# brain1_v11.net
KiCad netlist of a schematic drawn in EAGLE
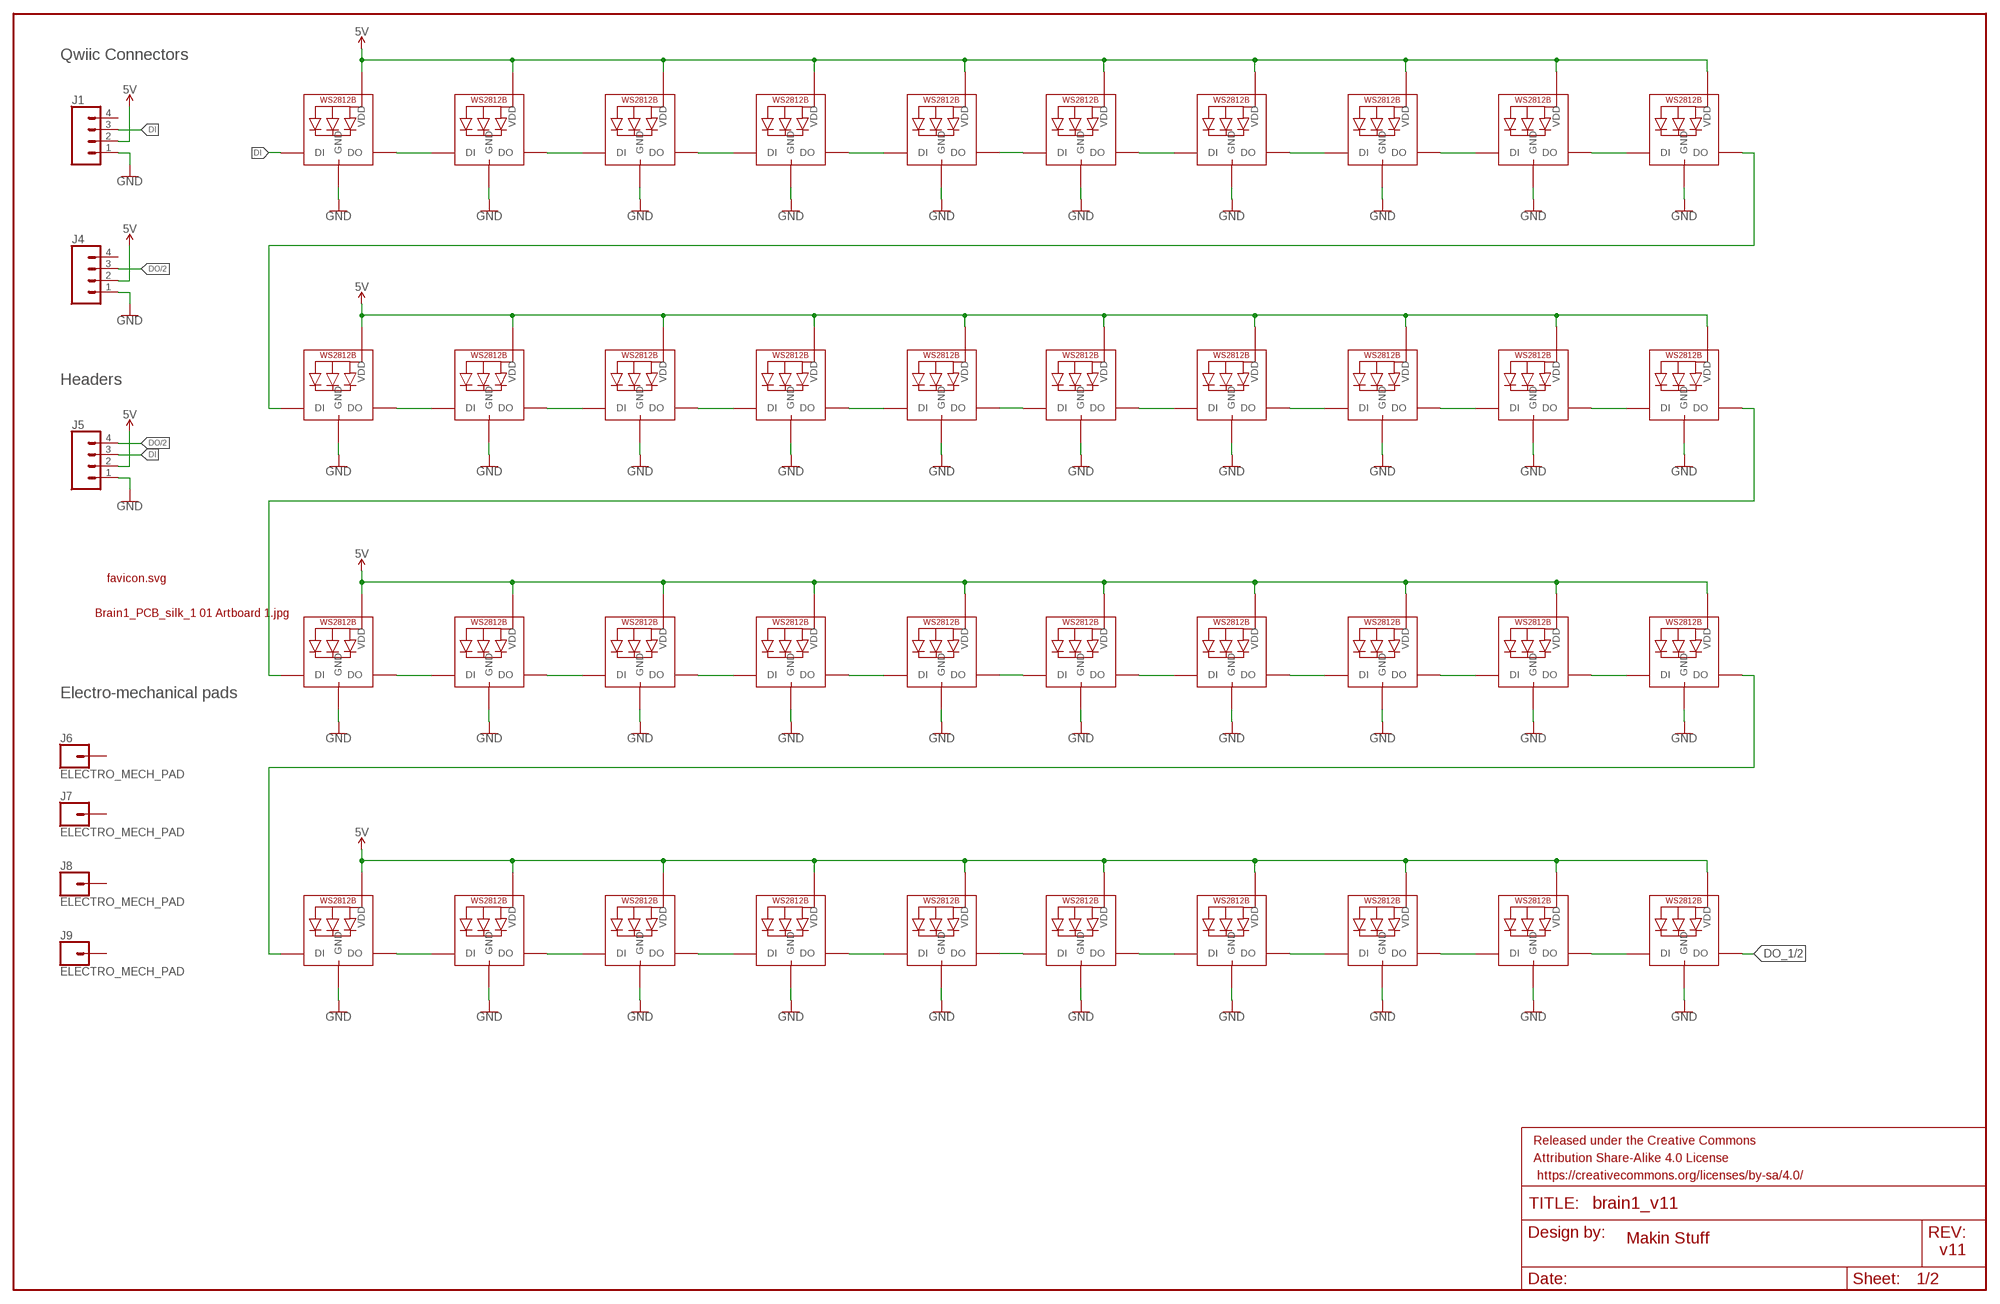
[diagram p0: schematic, sheet 1]
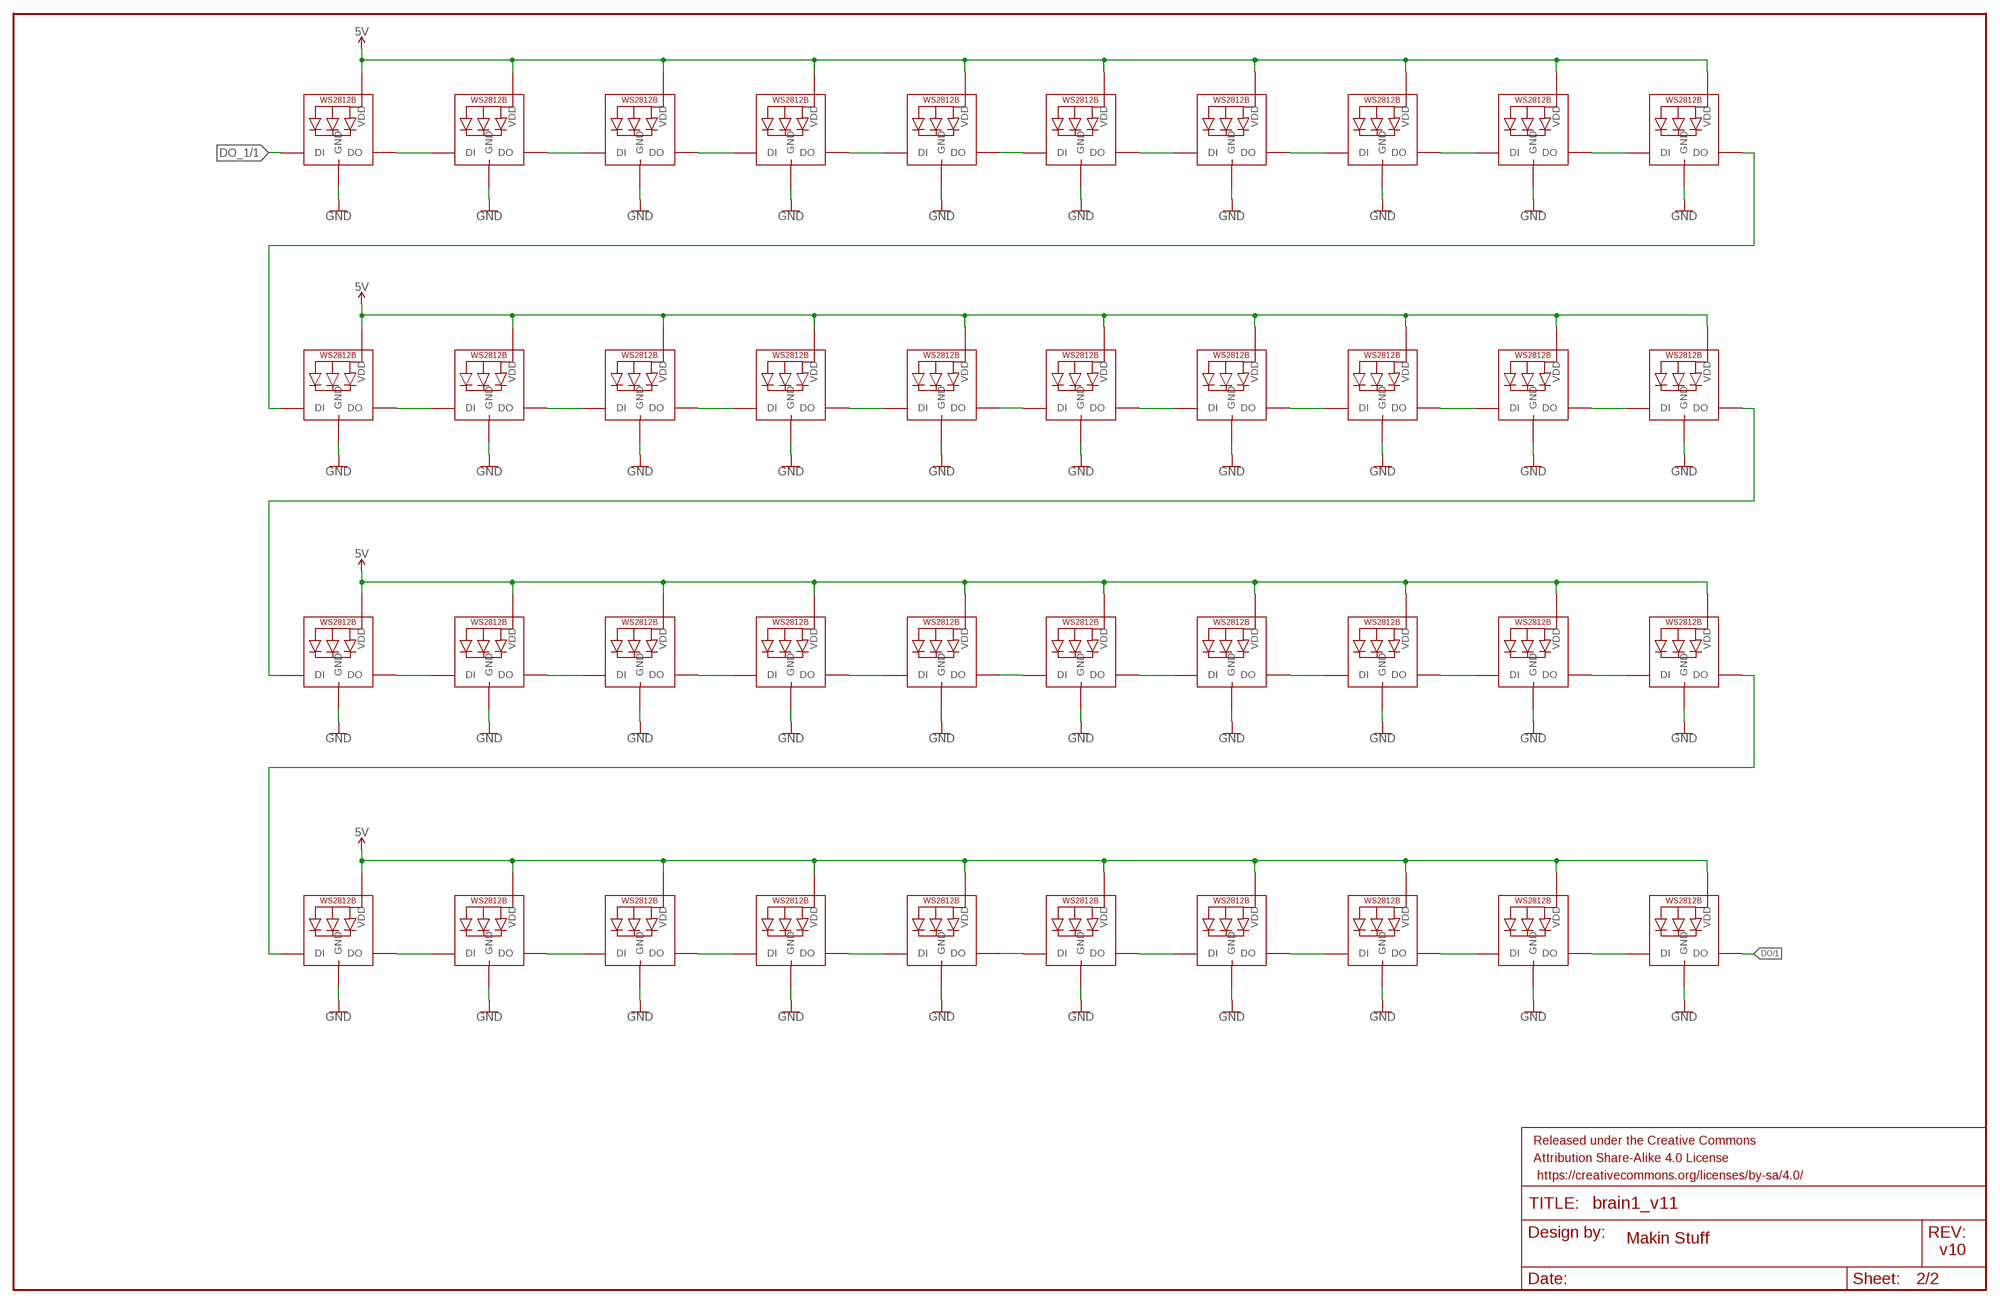
[diagram p1: schematic, sheet 2]

(export (version "E")
  (design (tool "Eeschema 10.0.6"))
  (components
    (comp (ref "FRAME1")
      (value "FRAME-LEDGER")
      (footprint "eagle-import:CREATIVE_COMMONS")
      (libsource (lib "eagle-import") (part "FRAME-LEDGER"))
    )
    (comp (ref "FRAME3")
      (value "FRAME-LEDGER")
      (footprint "eagle-import:CREATIVE_COMMONS")
      (libsource (lib "eagle-import") (part "FRAME-LEDGER"))
    )
    (comp (ref "LED41")
      (value "3.5X3.5_RGB_LED3.5X3.5")
      (footprint "eagle-import:3.5X3.5_RGB_LED")
      (libsource (lib "eagle-import") (part "3.5X3.5_RGB_LED3.5X3.5"))
    )
    (comp (ref "LED42")
      (value "3.5X3.5_RGB_LED3.5X3.5")
      (footprint "eagle-import:3.5X3.5_RGB_LED")
      (libsource (lib "eagle-import") (part "3.5X3.5_RGB_LED3.5X3.5"))
    )
    (comp (ref "LED43")
      (value "3.5X3.5_RGB_LED3.5X3.5")
      (footprint "eagle-import:3.5X3.5_RGB_LED")
      (libsource (lib "eagle-import") (part "3.5X3.5_RGB_LED3.5X3.5"))
    )
    (comp (ref "LED44")
      (value "3.5X3.5_RGB_LED3.5X3.5")
      (footprint "eagle-import:3.5X3.5_RGB_LED")
      (libsource (lib "eagle-import") (part "3.5X3.5_RGB_LED3.5X3.5"))
    )
    (comp (ref "LED45")
      (value "3.5X3.5_RGB_LED3.5X3.5")
      (footprint "eagle-import:3.5X3.5_RGB_LED")
      (libsource (lib "eagle-import") (part "3.5X3.5_RGB_LED3.5X3.5"))
    )
    (comp (ref "LED46")
      (value "3.5X3.5_RGB_LED3.5X3.5")
      (footprint "eagle-import:3.5X3.5_RGB_LED")
      (libsource (lib "eagle-import") (part "3.5X3.5_RGB_LED3.5X3.5"))
    )
    (comp (ref "LED47")
      (value "3.5X3.5_RGB_LED3.5X3.5")
      (footprint "eagle-import:3.5X3.5_RGB_LED")
      (libsource (lib "eagle-import") (part "3.5X3.5_RGB_LED3.5X3.5"))
    )
    (comp (ref "LED48")
      (value "3.5X3.5_RGB_LED3.5X3.5")
      (footprint "eagle-import:3.5X3.5_RGB_LED")
      (libsource (lib "eagle-import") (part "3.5X3.5_RGB_LED3.5X3.5"))
    )
    (comp (ref "LED49")
      (value "3.5X3.5_RGB_LED3.5X3.5")
      (footprint "eagle-import:3.5X3.5_RGB_LED")
      (libsource (lib "eagle-import") (part "3.5X3.5_RGB_LED3.5X3.5"))
    )
    (comp (ref "LED50")
      (value "3.5X3.5_RGB_LED3.5X3.5")
      (footprint "eagle-import:3.5X3.5_RGB_LED")
      (libsource (lib "eagle-import") (part "3.5X3.5_RGB_LED3.5X3.5"))
    )
    (comp (ref "LED51")
      (value "3.5X3.5_RGB_LED3.5X3.5")
      (footprint "eagle-import:3.5X3.5_RGB_LED")
      (libsource (lib "eagle-import") (part "3.5X3.5_RGB_LED3.5X3.5"))
    )
    (comp (ref "LED52")
      (value "3.5X3.5_RGB_LED3.5X3.5")
      (footprint "eagle-import:3.5X3.5_RGB_LED")
      (libsource (lib "eagle-import") (part "3.5X3.5_RGB_LED3.5X3.5"))
    )
    (comp (ref "LED53")
      (value "3.5X3.5_RGB_LED3.5X3.5")
      (footprint "eagle-import:3.5X3.5_RGB_LED")
      (libsource (lib "eagle-import") (part "3.5X3.5_RGB_LED3.5X3.5"))
    )
    (comp (ref "LED54")
      (value "3.5X3.5_RGB_LED3.5X3.5")
      (footprint "eagle-import:3.5X3.5_RGB_LED")
      (libsource (lib "eagle-import") (part "3.5X3.5_RGB_LED3.5X3.5"))
    )
    (comp (ref "LED55")
      (value "3.5X3.5_RGB_LED3.5X3.5")
      (footprint "eagle-import:3.5X3.5_RGB_LED")
      (libsource (lib "eagle-import") (part "3.5X3.5_RGB_LED3.5X3.5"))
    )
    (comp (ref "LED56")
      (value "3.5X3.5_RGB_LED3.5X3.5")
      (footprint "eagle-import:3.5X3.5_RGB_LED")
      (libsource (lib "eagle-import") (part "3.5X3.5_RGB_LED3.5X3.5"))
    )
    (comp (ref "LED57")
      (value "3.5X3.5_RGB_LED3.5X3.5")
      (footprint "eagle-import:3.5X3.5_RGB_LED")
      (libsource (lib "eagle-import") (part "3.5X3.5_RGB_LED3.5X3.5"))
    )
    (comp (ref "LED58")
      (value "3.5X3.5_RGB_LED3.5X3.5")
      (footprint "eagle-import:3.5X3.5_RGB_LED")
      (libsource (lib "eagle-import") (part "3.5X3.5_RGB_LED3.5X3.5"))
    )
    (comp (ref "LED59")
      (value "3.5X3.5_RGB_LED3.5X3.5")
      (footprint "eagle-import:3.5X3.5_RGB_LED")
      (libsource (lib "eagle-import") (part "3.5X3.5_RGB_LED3.5X3.5"))
    )
    (comp (ref "LED60")
      (value "3.5X3.5_RGB_LED3.5X3.5")
      (footprint "eagle-import:3.5X3.5_RGB_LED")
      (libsource (lib "eagle-import") (part "3.5X3.5_RGB_LED3.5X3.5"))
    )
    (comp (ref "LED61")
      (value "3.5X3.5_RGB_LED3.5X3.5")
      (footprint "eagle-import:3.5X3.5_RGB_LED")
      (libsource (lib "eagle-import") (part "3.5X3.5_RGB_LED3.5X3.5"))
    )
    (comp (ref "LED62")
      (value "3.5X3.5_RGB_LED3.5X3.5")
      (footprint "eagle-import:3.5X3.5_RGB_LED")
      (libsource (lib "eagle-import") (part "3.5X3.5_RGB_LED3.5X3.5"))
    )
    (comp (ref "LED63")
      (value "3.5X3.5_RGB_LED3.5X3.5")
      (footprint "eagle-import:3.5X3.5_RGB_LED")
      (libsource (lib "eagle-import") (part "3.5X3.5_RGB_LED3.5X3.5"))
    )
    (comp (ref "LED64")
      (value "3.5X3.5_RGB_LED3.5X3.5")
      (footprint "eagle-import:3.5X3.5_RGB_LED")
      (libsource (lib "eagle-import") (part "3.5X3.5_RGB_LED3.5X3.5"))
    )
    (comp (ref "LED65")
      (value "3.5X3.5_RGB_LED3.5X3.5")
      (footprint "eagle-import:3.5X3.5_RGB_LED")
      (libsource (lib "eagle-import") (part "3.5X3.5_RGB_LED3.5X3.5"))
    )
    (comp (ref "LED66")
      (value "3.5X3.5_RGB_LED3.5X3.5")
      (footprint "eagle-import:3.5X3.5_RGB_LED")
      (libsource (lib "eagle-import") (part "3.5X3.5_RGB_LED3.5X3.5"))
    )
    (comp (ref "LED67")
      (value "3.5X3.5_RGB_LED3.5X3.5")
      (footprint "eagle-import:3.5X3.5_RGB_LED")
      (libsource (lib "eagle-import") (part "3.5X3.5_RGB_LED3.5X3.5"))
    )
    (comp (ref "LED68")
      (value "3.5X3.5_RGB_LED3.5X3.5")
      (footprint "eagle-import:3.5X3.5_RGB_LED")
      (libsource (lib "eagle-import") (part "3.5X3.5_RGB_LED3.5X3.5"))
    )
    (comp (ref "LED69")
      (value "3.5X3.5_RGB_LED3.5X3.5")
      (footprint "eagle-import:3.5X3.5_RGB_LED")
      (libsource (lib "eagle-import") (part "3.5X3.5_RGB_LED3.5X3.5"))
    )
    (comp (ref "LED70")
      (value "3.5X3.5_RGB_LED3.5X3.5")
      (footprint "eagle-import:3.5X3.5_RGB_LED")
      (libsource (lib "eagle-import") (part "3.5X3.5_RGB_LED3.5X3.5"))
    )
    (comp (ref "LED71")
      (value "3.5X3.5_RGB_LED3.5X3.5")
      (footprint "eagle-import:3.5X3.5_RGB_LED")
      (libsource (lib "eagle-import") (part "3.5X3.5_RGB_LED3.5X3.5"))
    )
    (comp (ref "LED72")
      (value "3.5X3.5_RGB_LED3.5X3.5")
      (footprint "eagle-import:3.5X3.5_RGB_LED")
      (libsource (lib "eagle-import") (part "3.5X3.5_RGB_LED3.5X3.5"))
    )
    (comp (ref "LED73")
      (value "3.5X3.5_RGB_LED3.5X3.5")
      (footprint "eagle-import:3.5X3.5_RGB_LED")
      (libsource (lib "eagle-import") (part "3.5X3.5_RGB_LED3.5X3.5"))
    )
    (comp (ref "LED74")
      (value "3.5X3.5_RGB_LED3.5X3.5")
      (footprint "eagle-import:3.5X3.5_RGB_LED")
      (libsource (lib "eagle-import") (part "3.5X3.5_RGB_LED3.5X3.5"))
    )
    (comp (ref "LED75")
      (value "3.5X3.5_RGB_LED3.5X3.5")
      (footprint "eagle-import:3.5X3.5_RGB_LED")
      (libsource (lib "eagle-import") (part "3.5X3.5_RGB_LED3.5X3.5"))
    )
    (comp (ref "LED76")
      (value "3.5X3.5_RGB_LED3.5X3.5")
      (footprint "eagle-import:3.5X3.5_RGB_LED")
      (libsource (lib "eagle-import") (part "3.5X3.5_RGB_LED3.5X3.5"))
    )
    (comp (ref "LED77")
      (value "3.5X3.5_RGB_LED3.5X3.5")
      (footprint "eagle-import:3.5X3.5_RGB_LED")
      (libsource (lib "eagle-import") (part "3.5X3.5_RGB_LED3.5X3.5"))
    )
    (comp (ref "LED78")
      (value "3.5X3.5_RGB_LED3.5X3.5")
      (footprint "eagle-import:3.5X3.5_RGB_LED")
      (libsource (lib "eagle-import") (part "3.5X3.5_RGB_LED3.5X3.5"))
    )
    (comp (ref "LED79")
      (value "3.5X3.5_RGB_LED3.5X3.5")
      (footprint "eagle-import:3.5X3.5_RGB_LED")
      (libsource (lib "eagle-import") (part "3.5X3.5_RGB_LED3.5X3.5"))
    )
    (comp (ref "LED80")
      (value "3.5X3.5_RGB_LED3.5X3.5")
      (footprint "eagle-import:3.5X3.5_RGB_LED")
      (libsource (lib "eagle-import") (part "3.5X3.5_RGB_LED3.5X3.5"))
    )
    (comp (ref "FRAME2")
      (value "FRAME-LEDGER")
      (footprint "eagle-import:CREATIVE_COMMONS")
      (libsource (lib "eagle-import") (part "FRAME-LEDGER"))
    )
    (comp (ref "J1")
      (value "CONN_04SMD3")
      (footprint "eagle-import:JST04_1MM_RA")
      (libsource (lib "eagle-import") (part "CONN_04SMD3"))
    )
    (comp (ref "J4")
      (value "CONN_04SMD3")
      (footprint "eagle-import:JST04_1MM_RA")
      (libsource (lib "eagle-import") (part "CONN_04SMD3"))
    )
    (comp (ref "J5")
      (value "CONN_041X04_NO_SILK_NO_POP")
      (footprint "eagle-import:1X04_NO_SILK")
      (libsource (lib "eagle-import") (part "CONN_041X04_NO_SILK_NO_POP"))
    )
    (comp (ref "J6")
      (value "ELECTRO_MECH_PAD")
      (footprint "eagle-import:5X3_SOLDER_PAD")
      (libsource (lib "eagle-import") (part "ELECTRO_MECH_PAD"))
    )
    (comp (ref "J7")
      (value "ELECTRO_MECH_PAD")
      (footprint "eagle-import:5X3_SOLDER_PAD")
      (libsource (lib "eagle-import") (part "ELECTRO_MECH_PAD"))
    )
    (comp (ref "J8")
      (value "ELECTRO_MECH_PAD")
      (footprint "eagle-import:5X3_SOLDER_PAD")
      (libsource (lib "eagle-import") (part "ELECTRO_MECH_PAD"))
    )
    (comp (ref "J9")
      (value "ELECTRO_MECH_PAD")
      (footprint "eagle-import:5X3_SOLDER_PAD")
      (libsource (lib "eagle-import") (part "ELECTRO_MECH_PAD"))
    )
    (comp (ref "LED1")
      (value "3.5X3.5_RGB_LED3.5X3.5")
      (footprint "eagle-import:3.5X3.5_RGB_LED")
      (libsource (lib "eagle-import") (part "3.5X3.5_RGB_LED3.5X3.5"))
    )
    (comp (ref "LED2")
      (value "3.5X3.5_RGB_LED3.5X3.5")
      (footprint "eagle-import:3.5X3.5_RGB_LED")
      (libsource (lib "eagle-import") (part "3.5X3.5_RGB_LED3.5X3.5"))
    )
    (comp (ref "LED3")
      (value "3.5X3.5_RGB_LED3.5X3.5")
      (footprint "eagle-import:3.5X3.5_RGB_LED")
      (libsource (lib "eagle-import") (part "3.5X3.5_RGB_LED3.5X3.5"))
    )
    (comp (ref "LED4")
      (value "3.5X3.5_RGB_LED3.5X3.5")
      (footprint "eagle-import:3.5X3.5_RGB_LED")
      (libsource (lib "eagle-import") (part "3.5X3.5_RGB_LED3.5X3.5"))
    )
    (comp (ref "LED5")
      (value "3.5X3.5_RGB_LED3.5X3.5")
      (footprint "eagle-import:3.5X3.5_RGB_LED")
      (libsource (lib "eagle-import") (part "3.5X3.5_RGB_LED3.5X3.5"))
    )
    (comp (ref "LED6")
      (value "3.5X3.5_RGB_LED3.5X3.5")
      (footprint "eagle-import:3.5X3.5_RGB_LED")
      (libsource (lib "eagle-import") (part "3.5X3.5_RGB_LED3.5X3.5"))
    )
    (comp (ref "LED7")
      (value "3.5X3.5_RGB_LED3.5X3.5")
      (footprint "eagle-import:3.5X3.5_RGB_LED")
      (libsource (lib "eagle-import") (part "3.5X3.5_RGB_LED3.5X3.5"))
    )
    (comp (ref "LED8")
      (value "3.5X3.5_RGB_LED3.5X3.5")
      (footprint "eagle-import:3.5X3.5_RGB_LED")
      (libsource (lib "eagle-import") (part "3.5X3.5_RGB_LED3.5X3.5"))
    )
    (comp (ref "LED9")
      (value "3.5X3.5_RGB_LED3.5X3.5")
      (footprint "eagle-import:3.5X3.5_RGB_LED")
      (libsource (lib "eagle-import") (part "3.5X3.5_RGB_LED3.5X3.5"))
    )
    (comp (ref "LED10")
      (value "3.5X3.5_RGB_LED3.5X3.5")
      (footprint "eagle-import:3.5X3.5_RGB_LED")
      (libsource (lib "eagle-import") (part "3.5X3.5_RGB_LED3.5X3.5"))
    )
    (comp (ref "LED11")
      (value "3.5X3.5_RGB_LED3.5X3.5")
      (footprint "eagle-import:3.5X3.5_RGB_LED")
      (libsource (lib "eagle-import") (part "3.5X3.5_RGB_LED3.5X3.5"))
    )
    (comp (ref "LED12")
      (value "3.5X3.5_RGB_LED3.5X3.5")
      (footprint "eagle-import:3.5X3.5_RGB_LED")
      (libsource (lib "eagle-import") (part "3.5X3.5_RGB_LED3.5X3.5"))
    )
    (comp (ref "LED13")
      (value "3.5X3.5_RGB_LED3.5X3.5")
      (footprint "eagle-import:3.5X3.5_RGB_LED")
      (libsource (lib "eagle-import") (part "3.5X3.5_RGB_LED3.5X3.5"))
    )
    (comp (ref "LED14")
      (value "3.5X3.5_RGB_LED3.5X3.5")
      (footprint "eagle-import:3.5X3.5_RGB_LED")
      (libsource (lib "eagle-import") (part "3.5X3.5_RGB_LED3.5X3.5"))
    )
    (comp (ref "LED15")
      (value "3.5X3.5_RGB_LED3.5X3.5")
      (footprint "eagle-import:3.5X3.5_RGB_LED")
      (libsource (lib "eagle-import") (part "3.5X3.5_RGB_LED3.5X3.5"))
    )
    (comp (ref "LED16")
      (value "3.5X3.5_RGB_LED3.5X3.5")
      (footprint "eagle-import:3.5X3.5_RGB_LED")
      (libsource (lib "eagle-import") (part "3.5X3.5_RGB_LED3.5X3.5"))
    )
    (comp (ref "LED17")
      (value "3.5X3.5_RGB_LED3.5X3.5")
      (footprint "eagle-import:3.5X3.5_RGB_LED")
      (libsource (lib "eagle-import") (part "3.5X3.5_RGB_LED3.5X3.5"))
    )
    (comp (ref "LED18")
      (value "3.5X3.5_RGB_LED3.5X3.5")
      (footprint "eagle-import:3.5X3.5_RGB_LED")
      (libsource (lib "eagle-import") (part "3.5X3.5_RGB_LED3.5X3.5"))
    )
    (comp (ref "LED19")
      (value "3.5X3.5_RGB_LED3.5X3.5")
      (footprint "eagle-import:3.5X3.5_RGB_LED")
      (libsource (lib "eagle-import") (part "3.5X3.5_RGB_LED3.5X3.5"))
    )
    (comp (ref "LED20")
      (value "3.5X3.5_RGB_LED3.5X3.5")
      (footprint "eagle-import:3.5X3.5_RGB_LED")
      (libsource (lib "eagle-import") (part "3.5X3.5_RGB_LED3.5X3.5"))
    )
    (comp (ref "LED21")
      (value "3.5X3.5_RGB_LED3.5X3.5")
      (footprint "eagle-import:3.5X3.5_RGB_LED")
      (libsource (lib "eagle-import") (part "3.5X3.5_RGB_LED3.5X3.5"))
    )
    (comp (ref "LED22")
      (value "3.5X3.5_RGB_LED3.5X3.5")
      (footprint "eagle-import:3.5X3.5_RGB_LED")
      (libsource (lib "eagle-import") (part "3.5X3.5_RGB_LED3.5X3.5"))
    )
    (comp (ref "LED23")
      (value "3.5X3.5_RGB_LED3.5X3.5")
      (footprint "eagle-import:3.5X3.5_RGB_LED")
      (libsource (lib "eagle-import") (part "3.5X3.5_RGB_LED3.5X3.5"))
    )
    (comp (ref "LED24")
      (value "3.5X3.5_RGB_LED3.5X3.5")
      (footprint "eagle-import:3.5X3.5_RGB_LED")
      (libsource (lib "eagle-import") (part "3.5X3.5_RGB_LED3.5X3.5"))
    )
    (comp (ref "LED25")
      (value "3.5X3.5_RGB_LED3.5X3.5")
      (footprint "eagle-import:3.5X3.5_RGB_LED")
      (libsource (lib "eagle-import") (part "3.5X3.5_RGB_LED3.5X3.5"))
    )
    (comp (ref "LED26")
      (value "3.5X3.5_RGB_LED3.5X3.5")
      (footprint "eagle-import:3.5X3.5_RGB_LED")
      (libsource (lib "eagle-import") (part "3.5X3.5_RGB_LED3.5X3.5"))
    )
    (comp (ref "LED27")
      (value "3.5X3.5_RGB_LED3.5X3.5")
      (footprint "eagle-import:3.5X3.5_RGB_LED")
      (libsource (lib "eagle-import") (part "3.5X3.5_RGB_LED3.5X3.5"))
    )
    (comp (ref "LED28")
      (value "3.5X3.5_RGB_LED3.5X3.5")
      (footprint "eagle-import:3.5X3.5_RGB_LED")
      (libsource (lib "eagle-import") (part "3.5X3.5_RGB_LED3.5X3.5"))
    )
    (comp (ref "LED29")
      (value "3.5X3.5_RGB_LED3.5X3.5")
      (footprint "eagle-import:3.5X3.5_RGB_LED")
      (libsource (lib "eagle-import") (part "3.5X3.5_RGB_LED3.5X3.5"))
    )
    (comp (ref "LED30")
      (value "3.5X3.5_RGB_LED3.5X3.5")
      (footprint "eagle-import:3.5X3.5_RGB_LED")
      (libsource (lib "eagle-import") (part "3.5X3.5_RGB_LED3.5X3.5"))
    )
    (comp (ref "LED31")
      (value "3.5X3.5_RGB_LED3.5X3.5")
      (footprint "eagle-import:3.5X3.5_RGB_LED")
      (libsource (lib "eagle-import") (part "3.5X3.5_RGB_LED3.5X3.5"))
    )
    (comp (ref "LED32")
      (value "3.5X3.5_RGB_LED3.5X3.5")
      (footprint "eagle-import:3.5X3.5_RGB_LED")
      (libsource (lib "eagle-import") (part "3.5X3.5_RGB_LED3.5X3.5"))
    )
    (comp (ref "LED33")
      (value "3.5X3.5_RGB_LED3.5X3.5")
      (footprint "eagle-import:3.5X3.5_RGB_LED")
      (libsource (lib "eagle-import") (part "3.5X3.5_RGB_LED3.5X3.5"))
    )
    (comp (ref "LED34")
      (value "3.5X3.5_RGB_LED3.5X3.5")
      (footprint "eagle-import:3.5X3.5_RGB_LED")
      (libsource (lib "eagle-import") (part "3.5X3.5_RGB_LED3.5X3.5"))
    )
    (comp (ref "LED35")
      (value "3.5X3.5_RGB_LED3.5X3.5")
      (footprint "eagle-import:3.5X3.5_RGB_LED")
      (libsource (lib "eagle-import") (part "3.5X3.5_RGB_LED3.5X3.5"))
    )
    (comp (ref "LED36")
      (value "3.5X3.5_RGB_LED3.5X3.5")
      (footprint "eagle-import:3.5X3.5_RGB_LED")
      (libsource (lib "eagle-import") (part "3.5X3.5_RGB_LED3.5X3.5"))
    )
    (comp (ref "LED37")
      (value "3.5X3.5_RGB_LED3.5X3.5")
      (footprint "eagle-import:3.5X3.5_RGB_LED")
      (libsource (lib "eagle-import") (part "3.5X3.5_RGB_LED3.5X3.5"))
    )
    (comp (ref "LED38")
      (value "3.5X3.5_RGB_LED3.5X3.5")
      (footprint "eagle-import:3.5X3.5_RGB_LED")
      (libsource (lib "eagle-import") (part "3.5X3.5_RGB_LED3.5X3.5"))
    )
    (comp (ref "LED39")
      (value "3.5X3.5_RGB_LED3.5X3.5")
      (footprint "eagle-import:3.5X3.5_RGB_LED")
      (libsource (lib "eagle-import") (part "3.5X3.5_RGB_LED3.5X3.5"))
    )
    (comp (ref "LED40")
      (value "3.5X3.5_RGB_LED3.5X3.5")
      (footprint "eagle-import:3.5X3.5_RGB_LED")
      (libsource (lib "eagle-import") (part "3.5X3.5_RGB_LED3.5X3.5"))
    )
    (comp (ref "U$1")
      (value "FAVICON#SVG")
      (footprint "eagle-import:FAVICON#SVG")
      (libsource (lib "eagle-import") (part "FAVICON#SVG"))
    )
    (comp (ref "U$2")
      (value "BRAIN1_PCB_SILK_1_01_ARTBOARD_1#JPG")
      (footprint "eagle-import:BRAIN1_PCB_SILK_1_01_ARTBOARD_1#JPG")
      (libsource (lib "eagle-import") (part "BRAIN1_PCB_SILK_1_01_ARTBOARD_1#JPG"))
    )
  )
  (nets
    (net (code "1") (name "5V") (class "Default")
      (node (ref "J1") (pin "2") (pinfunction "2_2") (pintype "passive"))
      (node (ref "J4") (pin "2") (pinfunction "2_2") (pintype "passive"))
      (node (ref "J5") (pin "2") (pinfunction "2_2") (pintype "passive"))
      (node (ref "LED1") (pin "4") (pinfunction "VDD_4") (pintype "power_in"))
      (node (ref "LED10") (pin "4") (pinfunction "VDD_4") (pintype "power_in"))
      (node (ref "LED11") (pin "4") (pinfunction "VDD_4") (pintype "power_in"))
      (node (ref "LED12") (pin "4") (pinfunction "VDD_4") (pintype "power_in"))
      (node (ref "LED13") (pin "4") (pinfunction "VDD_4") (pintype "power_in"))
      (node (ref "LED14") (pin "4") (pinfunction "VDD_4") (pintype "power_in"))
      (node (ref "LED15") (pin "4") (pinfunction "VDD_4") (pintype "power_in"))
      (node (ref "LED16") (pin "4") (pinfunction "VDD_4") (pintype "power_in"))
      (node (ref "LED17") (pin "4") (pinfunction "VDD_4") (pintype "power_in"))
      (node (ref "LED18") (pin "4") (pinfunction "VDD_4") (pintype "power_in"))
      (node (ref "LED19") (pin "4") (pinfunction "VDD_4") (pintype "power_in"))
      (node (ref "LED2") (pin "4") (pinfunction "VDD_4") (pintype "power_in"))
      (node (ref "LED20") (pin "4") (pinfunction "VDD_4") (pintype "power_in"))
      (node (ref "LED21") (pin "4") (pinfunction "VDD_4") (pintype "power_in"))
      (node (ref "LED22") (pin "4") (pinfunction "VDD_4") (pintype "power_in"))
      (node (ref "LED23") (pin "4") (pinfunction "VDD_4") (pintype "power_in"))
      (node (ref "LED24") (pin "4") (pinfunction "VDD_4") (pintype "power_in"))
      (node (ref "LED25") (pin "4") (pinfunction "VDD_4") (pintype "power_in"))
      (node (ref "LED26") (pin "4") (pinfunction "VDD_4") (pintype "power_in"))
      (node (ref "LED27") (pin "4") (pinfunction "VDD_4") (pintype "power_in"))
      (node (ref "LED28") (pin "4") (pinfunction "VDD_4") (pintype "power_in"))
      (node (ref "LED29") (pin "4") (pinfunction "VDD_4") (pintype "power_in"))
      (node (ref "LED3") (pin "4") (pinfunction "VDD_4") (pintype "power_in"))
      (node (ref "LED30") (pin "4") (pinfunction "VDD_4") (pintype "power_in"))
      (node (ref "LED31") (pin "4") (pinfunction "VDD_4") (pintype "power_in"))
      (node (ref "LED32") (pin "4") (pinfunction "VDD_4") (pintype "power_in"))
      (node (ref "LED33") (pin "4") (pinfunction "VDD_4") (pintype "power_in"))
      (node (ref "LED34") (pin "4") (pinfunction "VDD_4") (pintype "power_in"))
      (node (ref "LED35") (pin "4") (pinfunction "VDD_4") (pintype "power_in"))
      (node (ref "LED36") (pin "4") (pinfunction "VDD_4") (pintype "power_in"))
      (node (ref "LED37") (pin "4") (pinfunction "VDD_4") (pintype "power_in"))
      (node (ref "LED38") (pin "4") (pinfunction "VDD_4") (pintype "power_in"))
      (node (ref "LED39") (pin "4") (pinfunction "VDD_4") (pintype "power_in"))
      (node (ref "LED4") (pin "4") (pinfunction "VDD_4") (pintype "power_in"))
      (node (ref "LED40") (pin "4") (pinfunction "VDD_4") (pintype "power_in"))
      (node (ref "LED41") (pin "4") (pinfunction "VDD_4") (pintype "power_in"))
      (node (ref "LED42") (pin "4") (pinfunction "VDD_4") (pintype "power_in"))
      (node (ref "LED43") (pin "4") (pinfunction "VDD_4") (pintype "power_in"))
      (node (ref "LED44") (pin "4") (pinfunction "VDD_4") (pintype "power_in"))
      (node (ref "LED45") (pin "4") (pinfunction "VDD_4") (pintype "power_in"))
      (node (ref "LED46") (pin "4") (pinfunction "VDD_4") (pintype "power_in"))
      (node (ref "LED47") (pin "4") (pinfunction "VDD_4") (pintype "power_in"))
      (node (ref "LED48") (pin "4") (pinfunction "VDD_4") (pintype "power_in"))
      (node (ref "LED49") (pin "4") (pinfunction "VDD_4") (pintype "power_in"))
      (node (ref "LED5") (pin "4") (pinfunction "VDD_4") (pintype "power_in"))
      (node (ref "LED50") (pin "4") (pinfunction "VDD_4") (pintype "power_in"))
      (node (ref "LED51") (pin "4") (pinfunction "VDD_4") (pintype "power_in"))
      (node (ref "LED52") (pin "4") (pinfunction "VDD_4") (pintype "power_in"))
      (node (ref "LED53") (pin "4") (pinfunction "VDD_4") (pintype "power_in"))
      (node (ref "LED54") (pin "4") (pinfunction "VDD_4") (pintype "power_in"))
      (node (ref "LED55") (pin "4") (pinfunction "VDD_4") (pintype "power_in"))
      (node (ref "LED56") (pin "4") (pinfunction "VDD_4") (pintype "power_in"))
      (node (ref "LED57") (pin "4") (pinfunction "VDD_4") (pintype "power_in"))
      (node (ref "LED58") (pin "4") (pinfunction "VDD_4") (pintype "power_in"))
      (node (ref "LED59") (pin "4") (pinfunction "VDD_4") (pintype "power_in"))
      (node (ref "LED6") (pin "4") (pinfunction "VDD_4") (pintype "power_in"))
      (node (ref "LED60") (pin "4") (pinfunction "VDD_4") (pintype "power_in"))
      (node (ref "LED61") (pin "4") (pinfunction "VDD_4") (pintype "power_in"))
      (node (ref "LED62") (pin "4") (pinfunction "VDD_4") (pintype "power_in"))
      (node (ref "LED63") (pin "4") (pinfunction "VDD_4") (pintype "power_in"))
      (node (ref "LED64") (pin "4") (pinfunction "VDD_4") (pintype "power_in"))
      (node (ref "LED65") (pin "4") (pinfunction "VDD_4") (pintype "power_in"))
      (node (ref "LED66") (pin "4") (pinfunction "VDD_4") (pintype "power_in"))
      (node (ref "LED67") (pin "4") (pinfunction "VDD_4") (pintype "power_in"))
      (node (ref "LED68") (pin "4") (pinfunction "VDD_4") (pintype "power_in"))
      (node (ref "LED69") (pin "4") (pinfunction "VDD_4") (pintype "power_in"))
      (node (ref "LED7") (pin "4") (pinfunction "VDD_4") (pintype "power_in"))
      (node (ref "LED70") (pin "4") (pinfunction "VDD_4") (pintype "power_in"))
      (node (ref "LED71") (pin "4") (pinfunction "VDD_4") (pintype "power_in"))
      (node (ref "LED72") (pin "4") (pinfunction "VDD_4") (pintype "power_in"))
      (node (ref "LED73") (pin "4") (pinfunction "VDD_4") (pintype "power_in"))
      (node (ref "LED74") (pin "4") (pinfunction "VDD_4") (pintype "power_in"))
      (node (ref "LED75") (pin "4") (pinfunction "VDD_4") (pintype "power_in"))
      (node (ref "LED76") (pin "4") (pinfunction "VDD_4") (pintype "power_in"))
      (node (ref "LED77") (pin "4") (pinfunction "VDD_4") (pintype "power_in"))
      (node (ref "LED78") (pin "4") (pinfunction "VDD_4") (pintype "power_in"))
      (node (ref "LED79") (pin "4") (pinfunction "VDD_4") (pintype "power_in"))
      (node (ref "LED8") (pin "4") (pinfunction "VDD_4") (pintype "power_in"))
      (node (ref "LED80") (pin "4") (pinfunction "VDD_4") (pintype "power_in"))
      (node (ref "LED9") (pin "4") (pinfunction "VDD_4") (pintype "power_in"))
    )
    (net (code "2") (name "DI") (class "Default")
      (node (ref "J1") (pin "3") (pinfunction "3_3") (pintype "passive"))
      (node (ref "J5") (pin "3") (pinfunction "3_3") (pintype "passive"))
      (node (ref "LED1") (pin "3") (pinfunction "DI_3") (pintype "input"))
    )
    (net (code "3") (name "DO") (class "Default")
      (node (ref "J4") (pin "3") (pinfunction "3_3") (pintype "passive"))
      (node (ref "J5") (pin "4") (pinfunction "4_4") (pintype "passive"))
      (node (ref "LED80") (pin "1") (pinfunction "DO_1") (pintype "output"))
    )
    (net (code "4") (name "DO_1") (class "Default")
      (node (ref "LED40") (pin "1") (pinfunction "DO_1") (pintype "output"))
      (node (ref "LED41") (pin "3") (pinfunction "DI_3") (pintype "input"))
    )
    (net (code "5") (name "GND") (class "Default")
      (node (ref "J1") (pin "1") (pinfunction "1_1") (pintype "passive"))
      (node (ref "J4") (pin "1") (pinfunction "1_1") (pintype "passive"))
      (node (ref "J5") (pin "1") (pinfunction "1_1") (pintype "passive"))
      (node (ref "LED1") (pin "2") (pinfunction "GND_2") (pintype "power_in"))
      (node (ref "LED10") (pin "2") (pinfunction "GND_2") (pintype "power_in"))
      (node (ref "LED11") (pin "2") (pinfunction "GND_2") (pintype "power_in"))
      (node (ref "LED12") (pin "2") (pinfunction "GND_2") (pintype "power_in"))
      (node (ref "LED13") (pin "2") (pinfunction "GND_2") (pintype "power_in"))
      (node (ref "LED14") (pin "2") (pinfunction "GND_2") (pintype "power_in"))
      (node (ref "LED15") (pin "2") (pinfunction "GND_2") (pintype "power_in"))
      (node (ref "LED16") (pin "2") (pinfunction "GND_2") (pintype "power_in"))
      (node (ref "LED17") (pin "2") (pinfunction "GND_2") (pintype "power_in"))
      (node (ref "LED18") (pin "2") (pinfunction "GND_2") (pintype "power_in"))
      (node (ref "LED19") (pin "2") (pinfunction "GND_2") (pintype "power_in"))
      (node (ref "LED2") (pin "2") (pinfunction "GND_2") (pintype "power_in"))
      (node (ref "LED20") (pin "2") (pinfunction "GND_2") (pintype "power_in"))
      (node (ref "LED21") (pin "2") (pinfunction "GND_2") (pintype "power_in"))
      (node (ref "LED22") (pin "2") (pinfunction "GND_2") (pintype "power_in"))
      (node (ref "LED23") (pin "2") (pinfunction "GND_2") (pintype "power_in"))
      (node (ref "LED24") (pin "2") (pinfunction "GND_2") (pintype "power_in"))
      (node (ref "LED25") (pin "2") (pinfunction "GND_2") (pintype "power_in"))
      (node (ref "LED26") (pin "2") (pinfunction "GND_2") (pintype "power_in"))
      (node (ref "LED27") (pin "2") (pinfunction "GND_2") (pintype "power_in"))
      (node (ref "LED28") (pin "2") (pinfunction "GND_2") (pintype "power_in"))
      (node (ref "LED29") (pin "2") (pinfunction "GND_2") (pintype "power_in"))
      (node (ref "LED3") (pin "2") (pinfunction "GND_2") (pintype "power_in"))
      (node (ref "LED30") (pin "2") (pinfunction "GND_2") (pintype "power_in"))
      (node (ref "LED31") (pin "2") (pinfunction "GND_2") (pintype "power_in"))
      (node (ref "LED32") (pin "2") (pinfunction "GND_2") (pintype "power_in"))
      (node (ref "LED33") (pin "2") (pinfunction "GND_2") (pintype "power_in"))
      (node (ref "LED34") (pin "2") (pinfunction "GND_2") (pintype "power_in"))
      (node (ref "LED35") (pin "2") (pinfunction "GND_2") (pintype "power_in"))
      (node (ref "LED36") (pin "2") (pinfunction "GND_2") (pintype "power_in"))
      (node (ref "LED37") (pin "2") (pinfunction "GND_2") (pintype "power_in"))
      (node (ref "LED38") (pin "2") (pinfunction "GND_2") (pintype "power_in"))
      (node (ref "LED39") (pin "2") (pinfunction "GND_2") (pintype "power_in"))
      (node (ref "LED4") (pin "2") (pinfunction "GND_2") (pintype "power_in"))
      (node (ref "LED40") (pin "2") (pinfunction "GND_2") (pintype "power_in"))
      (node (ref "LED41") (pin "2") (pinfunction "GND_2") (pintype "power_in"))
      (node (ref "LED42") (pin "2") (pinfunction "GND_2") (pintype "power_in"))
      (node (ref "LED43") (pin "2") (pinfunction "GND_2") (pintype "power_in"))
      (node (ref "LED44") (pin "2") (pinfunction "GND_2") (pintype "power_in"))
      (node (ref "LED45") (pin "2") (pinfunction "GND_2") (pintype "power_in"))
      (node (ref "LED46") (pin "2") (pinfunction "GND_2") (pintype "power_in"))
      (node (ref "LED47") (pin "2") (pinfunction "GND_2") (pintype "power_in"))
      (node (ref "LED48") (pin "2") (pinfunction "GND_2") (pintype "power_in"))
      (node (ref "LED49") (pin "2") (pinfunction "GND_2") (pintype "power_in"))
      (node (ref "LED5") (pin "2") (pinfunction "GND_2") (pintype "power_in"))
      (node (ref "LED50") (pin "2") (pinfunction "GND_2") (pintype "power_in"))
      (node (ref "LED51") (pin "2") (pinfunction "GND_2") (pintype "power_in"))
      (node (ref "LED52") (pin "2") (pinfunction "GND_2") (pintype "power_in"))
      (node (ref "LED53") (pin "2") (pinfunction "GND_2") (pintype "power_in"))
      (node (ref "LED54") (pin "2") (pinfunction "GND_2") (pintype "power_in"))
      (node (ref "LED55") (pin "2") (pinfunction "GND_2") (pintype "power_in"))
      (node (ref "LED56") (pin "2") (pinfunction "GND_2") (pintype "power_in"))
      (node (ref "LED57") (pin "2") (pinfunction "GND_2") (pintype "power_in"))
      (node (ref "LED58") (pin "2") (pinfunction "GND_2") (pintype "power_in"))
      (node (ref "LED59") (pin "2") (pinfunction "GND_2") (pintype "power_in"))
      (node (ref "LED6") (pin "2") (pinfunction "GND_2") (pintype "power_in"))
      (node (ref "LED60") (pin "2") (pinfunction "GND_2") (pintype "power_in"))
      (node (ref "LED61") (pin "2") (pinfunction "GND_2") (pintype "power_in"))
      (node (ref "LED62") (pin "2") (pinfunction "GND_2") (pintype "power_in"))
      (node (ref "LED63") (pin "2") (pinfunction "GND_2") (pintype "power_in"))
      (node (ref "LED64") (pin "2") (pinfunction "GND_2") (pintype "power_in"))
      (node (ref "LED65") (pin "2") (pinfunction "GND_2") (pintype "power_in"))
      (node (ref "LED66") (pin "2") (pinfunction "GND_2") (pintype "power_in"))
      (node (ref "LED67") (pin "2") (pinfunction "GND_2") (pintype "power_in"))
      (node (ref "LED68") (pin "2") (pinfunction "GND_2") (pintype "power_in"))
      (node (ref "LED69") (pin "2") (pinfunction "GND_2") (pintype "power_in"))
      (node (ref "LED7") (pin "2") (pinfunction "GND_2") (pintype "power_in"))
      (node (ref "LED70") (pin "2") (pinfunction "GND_2") (pintype "power_in"))
      (node (ref "LED71") (pin "2") (pinfunction "GND_2") (pintype "power_in"))
      (node (ref "LED72") (pin "2") (pinfunction "GND_2") (pintype "power_in"))
      (node (ref "LED73") (pin "2") (pinfunction "GND_2") (pintype "power_in"))
      (node (ref "LED74") (pin "2") (pinfunction "GND_2") (pintype "power_in"))
      (node (ref "LED75") (pin "2") (pinfunction "GND_2") (pintype "power_in"))
      (node (ref "LED76") (pin "2") (pinfunction "GND_2") (pintype "power_in"))
      (node (ref "LED77") (pin "2") (pinfunction "GND_2") (pintype "power_in"))
      (node (ref "LED78") (pin "2") (pinfunction "GND_2") (pintype "power_in"))
      (node (ref "LED79") (pin "2") (pinfunction "GND_2") (pintype "power_in"))
      (node (ref "LED8") (pin "2") (pinfunction "GND_2") (pintype "power_in"))
      (node (ref "LED80") (pin "2") (pinfunction "GND_2") (pintype "power_in"))
      (node (ref "LED9") (pin "2") (pinfunction "GND_2") (pintype "power_in"))
    )
    (net (code "6") (name "Net-(LED1-DO)") (class "Default")
      (node (ref "LED1") (pin "1") (pinfunction "DO_1") (pintype "output"))
      (node (ref "LED2") (pin "3") (pinfunction "DI_3") (pintype "input"))
    )
    (net (code "7") (name "Net-(LED2-DO)") (class "Default")
      (node (ref "LED2") (pin "1") (pinfunction "DO_1") (pintype "output"))
      (node (ref "LED3") (pin "3") (pinfunction "DI_3") (pintype "input"))
    )
    (net (code "8") (name "Net-(LED3-DO)") (class "Default")
      (node (ref "LED3") (pin "1") (pinfunction "DO_1") (pintype "output"))
      (node (ref "LED4") (pin "3") (pinfunction "DI_3") (pintype "input"))
    )
    (net (code "9") (name "Net-(LED4-DO)") (class "Default")
      (node (ref "LED4") (pin "1") (pinfunction "DO_1") (pintype "output"))
      (node (ref "LED5") (pin "3") (pinfunction "DI_3") (pintype "input"))
    )
    (net (code "10") (name "Net-(LED5-DO)") (class "Default")
      (node (ref "LED5") (pin "1") (pinfunction "DO_1") (pintype "output"))
      (node (ref "LED6") (pin "3") (pinfunction "DI_3") (pintype "input"))
    )
    (net (code "11") (name "Net-(LED6-DO)") (class "Default")
      (node (ref "LED6") (pin "1") (pinfunction "DO_1") (pintype "output"))
      (node (ref "LED7") (pin "3") (pinfunction "DI_3") (pintype "input"))
    )
    (net (code "12") (name "Net-(LED7-DO)") (class "Default")
      (node (ref "LED7") (pin "1") (pinfunction "DO_1") (pintype "output"))
      (node (ref "LED8") (pin "3") (pinfunction "DI_3") (pintype "input"))
    )
    (net (code "13") (name "Net-(LED8-DO)") (class "Default")
      (node (ref "LED8") (pin "1") (pinfunction "DO_1") (pintype "output"))
      (node (ref "LED9") (pin "3") (pinfunction "DI_3") (pintype "input"))
    )
    (net (code "14") (name "Net-(LED10-DI)") (class "Default")
      (node (ref "LED10") (pin "3") (pinfunction "DI_3") (pintype "input"))
      (node (ref "LED9") (pin "1") (pinfunction "DO_1") (pintype "output"))
    )
    (net (code "15") (name "Net-(LED10-DO)") (class "Default")
      (node (ref "LED10") (pin "1") (pinfunction "DO_1") (pintype "output"))
      (node (ref "LED11") (pin "3") (pinfunction "DI_3") (pintype "input"))
    )
    (net (code "16") (name "Net-(LED11-DO)") (class "Default")
      (node (ref "LED11") (pin "1") (pinfunction "DO_1") (pintype "output"))
      (node (ref "LED12") (pin "3") (pinfunction "DI_3") (pintype "input"))
    )
    (net (code "17") (name "Net-(LED12-DO)") (class "Default")
      (node (ref "LED12") (pin "1") (pinfunction "DO_1") (pintype "output"))
      (node (ref "LED13") (pin "3") (pinfunction "DI_3") (pintype "input"))
    )
    (net (code "18") (name "Net-(LED13-DO)") (class "Default")
      (node (ref "LED13") (pin "1") (pinfunction "DO_1") (pintype "output"))
      (node (ref "LED14") (pin "3") (pinfunction "DI_3") (pintype "input"))
    )
    (net (code "19") (name "Net-(LED14-DO)") (class "Default")
      (node (ref "LED14") (pin "1") (pinfunction "DO_1") (pintype "output"))
      (node (ref "LED15") (pin "3") (pinfunction "DI_3") (pintype "input"))
    )
    (net (code "20") (name "Net-(LED15-DO)") (class "Default")
      (node (ref "LED15") (pin "1") (pinfunction "DO_1") (pintype "output"))
      (node (ref "LED16") (pin "3") (pinfunction "DI_3") (pintype "input"))
    )
    (net (code "21") (name "Net-(LED16-DO)") (class "Default")
      (node (ref "LED16") (pin "1") (pinfunction "DO_1") (pintype "output"))
      (node (ref "LED17") (pin "3") (pinfunction "DI_3") (pintype "input"))
    )
    (net (code "22") (name "Net-(LED17-DO)") (class "Default")
      (node (ref "LED17") (pin "1") (pinfunction "DO_1") (pintype "output"))
      (node (ref "LED18") (pin "3") (pinfunction "DI_3") (pintype "input"))
    )
    (net (code "23") (name "Net-(LED18-DO)") (class "Default")
      (node (ref "LED18") (pin "1") (pinfunction "DO_1") (pintype "output"))
      (node (ref "LED19") (pin "3") (pinfunction "DI_3") (pintype "input"))
    )
    (net (code "24") (name "Net-(LED19-DO)") (class "Default")
      (node (ref "LED19") (pin "1") (pinfunction "DO_1") (pintype "output"))
      (node (ref "LED20") (pin "3") (pinfunction "DI_3") (pintype "input"))
    )
    (net (code "25") (name "Net-(LED20-DO)") (class "Default")
      (node (ref "LED20") (pin "1") (pinfunction "DO_1") (pintype "output"))
      (node (ref "LED21") (pin "3") (pinfunction "DI_3") (pintype "input"))
    )
    (net (code "26") (name "Net-(LED21-DO)") (class "Default")
      (node (ref "LED21") (pin "1") (pinfunction "DO_1") (pintype "output"))
      (node (ref "LED22") (pin "3") (pinfunction "DI_3") (pintype "input"))
    )
    (net (code "27") (name "Net-(LED22-DO)") (class "Default")
      (node (ref "LED22") (pin "1") (pinfunction "DO_1") (pintype "output"))
      (node (ref "LED23") (pin "3") (pinfunction "DI_3") (pintype "input"))
    )
    (net (code "28") (name "Net-(LED23-DO)") (class "Default")
      (node (ref "LED23") (pin "1") (pinfunction "DO_1") (pintype "output"))
      (node (ref "LED24") (pin "3") (pinfunction "DI_3") (pintype "input"))
    )
    (net (code "29") (name "Net-(LED24-DO)") (class "Default")
      (node (ref "LED24") (pin "1") (pinfunction "DO_1") (pintype "output"))
      (node (ref "LED25") (pin "3") (pinfunction "DI_3") (pintype "input"))
    )
    (net (code "30") (name "Net-(LED25-DO)") (class "Default")
      (node (ref "LED25") (pin "1") (pinfunction "DO_1") (pintype "output"))
      (node (ref "LED26") (pin "3") (pinfunction "DI_3") (pintype "input"))
    )
    (net (code "31") (name "Net-(LED26-DO)") (class "Default")
      (node (ref "LED26") (pin "1") (pinfunction "DO_1") (pintype "output"))
      (node (ref "LED27") (pin "3") (pinfunction "DI_3") (pintype "input"))
    )
    (net (code "32") (name "Net-(LED27-DO)") (class "Default")
      (node (ref "LED27") (pin "1") (pinfunction "DO_1") (pintype "output"))
      (node (ref "LED28") (pin "3") (pinfunction "DI_3") (pintype "input"))
    )
    (net (code "33") (name "Net-(LED28-DO)") (class "Default")
      (node (ref "LED28") (pin "1") (pinfunction "DO_1") (pintype "output"))
      (node (ref "LED29") (pin "3") (pinfunction "DI_3") (pintype "input"))
    )
    (net (code "34") (name "Net-(LED29-DO)") (class "Default")
      (node (ref "LED29") (pin "1") (pinfunction "DO_1") (pintype "output"))
      (node (ref "LED30") (pin "3") (pinfunction "DI_3") (pintype "input"))
    )
    (net (code "35") (name "Net-(LED30-DO)") (class "Default")
      (node (ref "LED30") (pin "1") (pinfunction "DO_1") (pintype "output"))
      (node (ref "LED31") (pin "3") (pinfunction "DI_3") (pintype "input"))
    )
    (net (code "36") (name "Net-(LED31-DO)") (class "Default")
      (node (ref "LED31") (pin "1") (pinfunction "DO_1") (pintype "output"))
      (node (ref "LED32") (pin "3") (pinfunction "DI_3") (pintype "input"))
    )
    (net (code "37") (name "Net-(LED32-DO)") (class "Default")
      (node (ref "LED32") (pin "1") (pinfunction "DO_1") (pintype "output"))
      (node (ref "LED33") (pin "3") (pinfunction "DI_3") (pintype "input"))
    )
    (net (code "38") (name "Net-(LED33-DO)") (class "Default")
      (node (ref "LED33") (pin "1") (pinfunction "DO_1") (pintype "output"))
      (node (ref "LED34") (pin "3") (pinfunction "DI_3") (pintype "input"))
    )
    (net (code "39") (name "Net-(LED34-DO)") (class "Default")
      (node (ref "LED34") (pin "1") (pinfunction "DO_1") (pintype "output"))
      (node (ref "LED35") (pin "3") (pinfunction "DI_3") (pintype "input"))
    )
    (net (code "40") (name "Net-(LED35-DO)") (class "Default")
      (node (ref "LED35") (pin "1") (pinfunction "DO_1") (pintype "output"))
      (node (ref "LED36") (pin "3") (pinfunction "DI_3") (pintype "input"))
    )
    (net (code "41") (name "Net-(LED36-DO)") (class "Default")
      (node (ref "LED36") (pin "1") (pinfunction "DO_1") (pintype "output"))
      (node (ref "LED37") (pin "3") (pinfunction "DI_3") (pintype "input"))
    )
    (net (code "42") (name "Net-(LED37-DO)") (class "Default")
      (node (ref "LED37") (pin "1") (pinfunction "DO_1") (pintype "output"))
      (node (ref "LED38") (pin "3") (pinfunction "DI_3") (pintype "input"))
    )
    (net (code "43") (name "Net-(LED38-DO)") (class "Default")
      (node (ref "LED38") (pin "1") (pinfunction "DO_1") (pintype "output"))
      (node (ref "LED39") (pin "3") (pinfunction "DI_3") (pintype "input"))
    )
    (net (code "44") (name "Net-(LED39-DO)") (class "Default")
      (node (ref "LED39") (pin "1") (pinfunction "DO_1") (pintype "output"))
      (node (ref "LED40") (pin "3") (pinfunction "DI_3") (pintype "input"))
    )
    (net (code "45") (name "Net-(LED41-DO)") (class "Default")
      (node (ref "LED41") (pin "1") (pinfunction "DO_1") (pintype "output"))
      (node (ref "LED42") (pin "3") (pinfunction "DI_3") (pintype "input"))
    )
    (net (code "46") (name "Net-(LED42-DO)") (class "Default")
      (node (ref "LED42") (pin "1") (pinfunction "DO_1") (pintype "output"))
      (node (ref "LED43") (pin "3") (pinfunction "DI_3") (pintype "input"))
    )
    (net (code "47") (name "Net-(LED43-DO)") (class "Default")
      (node (ref "LED43") (pin "1") (pinfunction "DO_1") (pintype "output"))
      (node (ref "LED44") (pin "3") (pinfunction "DI_3") (pintype "input"))
    )
    (net (code "48") (name "Net-(LED44-DO)") (class "Default")
      (node (ref "LED44") (pin "1") (pinfunction "DO_1") (pintype "output"))
      (node (ref "LED45") (pin "3") (pinfunction "DI_3") (pintype "input"))
    )
    (net (code "49") (name "Net-(LED45-DO)") (class "Default")
      (node (ref "LED45") (pin "1") (pinfunction "DO_1") (pintype "output"))
      (node (ref "LED46") (pin "3") (pinfunction "DI_3") (pintype "input"))
    )
    (net (code "50") (name "Net-(LED46-DO)") (class "Default")
      (node (ref "LED46") (pin "1") (pinfunction "DO_1") (pintype "output"))
      (node (ref "LED47") (pin "3") (pinfunction "DI_3") (pintype "input"))
    )
    (net (code "51") (name "Net-(LED47-DO)") (class "Default")
      (node (ref "LED47") (pin "1") (pinfunction "DO_1") (pintype "output"))
      (node (ref "LED48") (pin "3") (pinfunction "DI_3") (pintype "input"))
    )
    (net (code "52") (name "Net-(LED48-DO)") (class "Default")
      (node (ref "LED48") (pin "1") (pinfunction "DO_1") (pintype "output"))
      (node (ref "LED49") (pin "3") (pinfunction "DI_3") (pintype "input"))
    )
    (net (code "53") (name "Net-(LED49-DO)") (class "Default")
      (node (ref "LED49") (pin "1") (pinfunction "DO_1") (pintype "output"))
      (node (ref "LED50") (pin "3") (pinfunction "DI_3") (pintype "input"))
    )
    (net (code "54") (name "Net-(LED50-DO)") (class "Default")
      (node (ref "LED50") (pin "1") (pinfunction "DO_1") (pintype "output"))
      (node (ref "LED51") (pin "3") (pinfunction "DI_3") (pintype "input"))
    )
    (net (code "55") (name "Net-(LED51-DO)") (class "Default")
      (node (ref "LED51") (pin "1") (pinfunction "DO_1") (pintype "output"))
      (node (ref "LED52") (pin "3") (pinfunction "DI_3") (pintype "input"))
    )
    (net (code "56") (name "Net-(LED52-DO)") (class "Default")
      (node (ref "LED52") (pin "1") (pinfunction "DO_1") (pintype "output"))
      (node (ref "LED53") (pin "3") (pinfunction "DI_3") (pintype "input"))
    )
    (net (code "57") (name "Net-(LED53-DO)") (class "Default")
      (node (ref "LED53") (pin "1") (pinfunction "DO_1") (pintype "output"))
      (node (ref "LED54") (pin "3") (pinfunction "DI_3") (pintype "input"))
    )
    (net (code "58") (name "Net-(LED54-DO)") (class "Default")
      (node (ref "LED54") (pin "1") (pinfunction "DO_1") (pintype "output"))
      (node (ref "LED55") (pin "3") (pinfunction "DI_3") (pintype "input"))
    )
    (net (code "59") (name "Net-(LED55-DO)") (class "Default")
      (node (ref "LED55") (pin "1") (pinfunction "DO_1") (pintype "output"))
      (node (ref "LED56") (pin "3") (pinfunction "DI_3") (pintype "input"))
    )
    (net (code "60") (name "Net-(LED56-DO)") (class "Default")
      (node (ref "LED56") (pin "1") (pinfunction "DO_1") (pintype "output"))
      (node (ref "LED57") (pin "3") (pinfunction "DI_3") (pintype "input"))
    )
    (net (code "61") (name "Net-(LED57-DO)") (class "Default")
      (node (ref "LED57") (pin "1") (pinfunction "DO_1") (pintype "output"))
      (node (ref "LED58") (pin "3") (pinfunction "DI_3") (pintype "input"))
    )
    (net (code "62") (name "Net-(LED58-DO)") (class "Default")
      (node (ref "LED58") (pin "1") (pinfunction "DO_1") (pintype "output"))
      (node (ref "LED59") (pin "3") (pinfunction "DI_3") (pintype "input"))
    )
    (net (code "63") (name "Net-(LED59-DO)") (class "Default")
      (node (ref "LED59") (pin "1") (pinfunction "DO_1") (pintype "output"))
      (node (ref "LED60") (pin "3") (pinfunction "DI_3") (pintype "input"))
    )
    (net (code "64") (name "Net-(LED60-DO)") (class "Default")
      (node (ref "LED60") (pin "1") (pinfunction "DO_1") (pintype "output"))
      (node (ref "LED61") (pin "3") (pinfunction "DI_3") (pintype "input"))
    )
    (net (code "65") (name "Net-(LED61-DO)") (class "Default")
      (node (ref "LED61") (pin "1") (pinfunction "DO_1") (pintype "output"))
      (node (ref "LED62") (pin "3") (pinfunction "DI_3") (pintype "input"))
    )
    (net (code "66") (name "Net-(LED62-DO)") (class "Default")
      (node (ref "LED62") (pin "1") (pinfunction "DO_1") (pintype "output"))
      (node (ref "LED63") (pin "3") (pinfunction "DI_3") (pintype "input"))
    )
    (net (code "67") (name "Net-(LED63-DO)") (class "Default")
      (node (ref "LED63") (pin "1") (pinfunction "DO_1") (pintype "output"))
      (node (ref "LED64") (pin "3") (pinfunction "DI_3") (pintype "input"))
    )
    (net (code "68") (name "Net-(LED64-DO)") (class "Default")
      (node (ref "LED64") (pin "1") (pinfunction "DO_1") (pintype "output"))
      (node (ref "LED65") (pin "3") (pinfunction "DI_3") (pintype "input"))
    )
    (net (code "69") (name "Net-(LED65-DO)") (class "Default")
      (node (ref "LED65") (pin "1") (pinfunction "DO_1") (pintype "output"))
      (node (ref "LED66") (pin "3") (pinfunction "DI_3") (pintype "input"))
    )
    (net (code "70") (name "Net-(LED66-DO)") (class "Default")
      (node (ref "LED66") (pin "1") (pinfunction "DO_1") (pintype "output"))
      (node (ref "LED67") (pin "3") (pinfunction "DI_3") (pintype "input"))
    )
    (net (code "71") (name "Net-(LED67-DO)") (class "Default")
      (node (ref "LED67") (pin "1") (pinfunction "DO_1") (pintype "output"))
      (node (ref "LED68") (pin "3") (pinfunction "DI_3") (pintype "input"))
    )
    (net (code "72") (name "Net-(LED68-DO)") (class "Default")
      (node (ref "LED68") (pin "1") (pinfunction "DO_1") (pintype "output"))
      (node (ref "LED69") (pin "3") (pinfunction "DI_3") (pintype "input"))
    )
    (net (code "73") (name "Net-(LED69-DO)") (class "Default")
      (node (ref "LED69") (pin "1") (pinfunction "DO_1") (pintype "output"))
      (node (ref "LED70") (pin "3") (pinfunction "DI_3") (pintype "input"))
    )
    (net (code "74") (name "Net-(LED70-DO)") (class "Default")
      (node (ref "LED70") (pin "1") (pinfunction "DO_1") (pintype "output"))
      (node (ref "LED71") (pin "3") (pinfunction "DI_3") (pintype "input"))
    )
    (net (code "75") (name "Net-(LED71-DO)") (class "Default")
      (node (ref "LED71") (pin "1") (pinfunction "DO_1") (pintype "output"))
      (node (ref "LED72") (pin "3") (pinfunction "DI_3") (pintype "input"))
    )
    (net (code "76") (name "Net-(LED72-DO)") (class "Default")
      (node (ref "LED72") (pin "1") (pinfunction "DO_1") (pintype "output"))
      (node (ref "LED73") (pin "3") (pinfunction "DI_3") (pintype "input"))
    )
    (net (code "77") (name "Net-(LED73-DO)") (class "Default")
      (node (ref "LED73") (pin "1") (pinfunction "DO_1") (pintype "output"))
      (node (ref "LED74") (pin "3") (pinfunction "DI_3") (pintype "input"))
    )
    (net (code "78") (name "Net-(LED74-DO)") (class "Default")
      (node (ref "LED74") (pin "1") (pinfunction "DO_1") (pintype "output"))
      (node (ref "LED75") (pin "3") (pinfunction "DI_3") (pintype "input"))
    )
    (net (code "79") (name "Net-(LED75-DO)") (class "Default")
      (node (ref "LED75") (pin "1") (pinfunction "DO_1") (pintype "output"))
      (node (ref "LED76") (pin "3") (pinfunction "DI_3") (pintype "input"))
    )
    (net (code "80") (name "Net-(LED76-DO)") (class "Default")
      (node (ref "LED76") (pin "1") (pinfunction "DO_1") (pintype "output"))
      (node (ref "LED77") (pin "3") (pinfunction "DI_3") (pintype "input"))
    )
    (net (code "81") (name "Net-(LED77-DO)") (class "Default")
      (node (ref "LED77") (pin "1") (pinfunction "DO_1") (pintype "output"))
      (node (ref "LED78") (pin "3") (pinfunction "DI_3") (pintype "input"))
    )
    (net (code "82") (name "Net-(LED78-DO)") (class "Default")
      (node (ref "LED78") (pin "1") (pinfunction "DO_1") (pintype "output"))
      (node (ref "LED79") (pin "3") (pinfunction "DI_3") (pintype "input"))
    )
    (net (code "83") (name "Net-(LED79-DO)") (class "Default")
      (node (ref "LED79") (pin "1") (pinfunction "DO_1") (pintype "output"))
      (node (ref "LED80") (pin "3") (pinfunction "DI_3") (pintype "input"))
    )
    (net (code "84") (name "unconnected-(J1-Pad4)") (class "Default")
      (node (ref "J1") (pin "4") (pinfunction "4_4") (pintype "passive"))
    )
    (net (code "85") (name "unconnected-(J4-Pad4)") (class "Default")
      (node (ref "J4") (pin "4") (pinfunction "4_4") (pintype "passive"))
    )
    (net (code "86") (name "unconnected-(J6-1-PadP$1)") (class "Default")
      (node (ref "J6") (pin "P$1") (pinfunction "1_P$1") (pintype "passive"))
    )
    (net (code "87") (name "unconnected-(J7-1-PadP$1)") (class "Default")
      (node (ref "J7") (pin "P$1") (pinfunction "1_P$1") (pintype "passive"))
    )
    (net (code "88") (name "unconnected-(J8-1-PadP$1)") (class "Default")
      (node (ref "J8") (pin "P$1") (pinfunction "1_P$1") (pintype "passive"))
    )
    (net (code "89") (name "unconnected-(J9-1-PadP$1)") (class "Default")
      (node (ref "J9") (pin "P$1") (pinfunction "1_P$1") (pintype "passive"))
    )
  )
)
